# hall_sensor100a.net
KiCad netlist of a schematic drawn in EAGLE
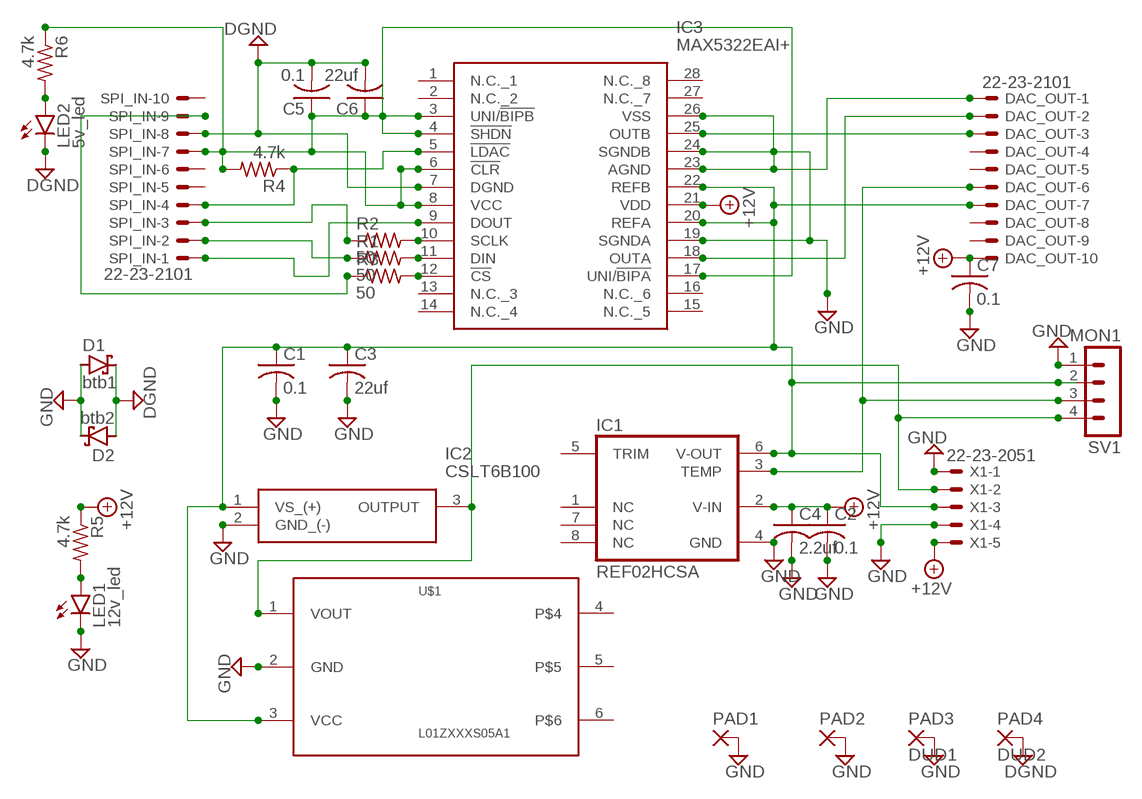
[diagram p0: schematic, sheet 1]

(export (version "E")
  (design (tool "Eeschema 10.0.6"))
  (components
    (comp (ref "C1")
      (value "0.1")
      (footprint "eagle-import:C0805")
      (libsource (lib "eagle-import") (part "C-USC0805"))
    )
    (comp (ref "C2")
      (value "0.1")
      (footprint "eagle-import:C0805")
      (libsource (lib "eagle-import") (part "C-USC0805"))
    )
    (comp (ref "C3")
      (value "22uf")
      (footprint "eagle-import:C0805")
      (libsource (lib "eagle-import") (part "C-USC0805"))
    )
    (comp (ref "C4")
      (value "2.2uf")
      (footprint "eagle-import:C0805")
      (libsource (lib "eagle-import") (part "C-USC0805"))
    )
    (comp (ref "C5")
      (value "0.1")
      (footprint "eagle-import:C0805")
      (libsource (lib "eagle-import") (part "C-USC0805"))
    )
    (comp (ref "C6")
      (value "22uf")
      (footprint "eagle-import:C0805")
      (libsource (lib "eagle-import") (part "C-USC0805"))
    )
    (comp (ref "C7")
      (value "0.1")
      (footprint "eagle-import:C0805")
      (libsource (lib "eagle-import") (part "C-USC0805"))
    )
    (comp (ref "D1")
      (value "btb1")
      (footprint "eagle-import:DO35-7")
      (libsource (lib "eagle-import") (part "SCHOTTKY-DIODEDO35-7"))
    )
    (comp (ref "D2")
      (value "btb2")
      (footprint "eagle-import:DO35-7")
      (libsource (lib "eagle-import") (part "SCHOTTKY-DIODEDO35-7"))
    )
    (comp (ref "DAC_OUT")
      (value "22-23-2101")
      (footprint "eagle-import:22-23-2101")
      (fields (field (name "MF") "MOLEX"))
      (libsource (lib "eagle-import") (part "22-23-2101"))
    )
    (comp (ref "IC1")
      (value "REF02HCSA")
      (footprint "eagle-import:SO08")
      (libsource (lib "eagle-import") (part "REF02HCSA"))
    )
    (comp (ref "IC2")
      (value "CSLT6B100")
      (footprint "eagle-import:CSLT6B100")
      (fields (field (name "MOUSER_PART_NUMBER") "785-CSLT6B100"))
      (libsource (lib "eagle-import") (part "CSLT6B100"))
    )
    (comp (ref "IC3")
      (value "MAX5322EAI+")
      (footprint "eagle-import:SOP65P778X199-28N")
      (fields (field (name "MOUSER_PART_NUMBER") "700-MAX5322EAI") (field (name "RS_PART_NUMBER") "7997645P"))
      (libsource (lib "eagle-import") (part "MAX5322EAI+"))
    )
    (comp (ref "LED1")
      (value "12v_led")
      (footprint "eagle-import:CHIPLED_1206")
      (libsource (lib "eagle-import") (part "LEDCHIPLED_1206"))
    )
    (comp (ref "LED2")
      (value "5v_led")
      (footprint "eagle-import:CHIPLED_1206")
      (libsource (lib "eagle-import") (part "LEDCHIPLED_1206"))
    )
    (comp (ref "PAD1")
      (value "2,15/1,0")
      (footprint "eagle-import:2,15_1,0")
      (libsource (lib "eagle-import") (part "2,15/1,0"))
    )
    (comp (ref "PAD2")
      (value "2,15/1,0")
      (footprint "eagle-import:2,15_1,0")
      (libsource (lib "eagle-import") (part "2,15/1,0"))
    )
    (comp (ref "PAD3")
      (value "DUD1")
      (footprint "eagle-import:2,15_1,0")
      (libsource (lib "eagle-import") (part "2,15/1,0"))
    )
    (comp (ref "PAD4")
      (value "DUD2")
      (footprint "eagle-import:2,15_1,0")
      (libsource (lib "eagle-import") (part "2,15/1,0"))
    )
    (comp (ref "R1")
      (value "50")
      (footprint "eagle-import:M0805")
      (libsource (lib "eagle-import") (part "R-US_M0805"))
    )
    (comp (ref "R2")
      (value "50")
      (footprint "eagle-import:M0805")
      (libsource (lib "eagle-import") (part "R-US_M0805"))
    )
    (comp (ref "R3")
      (value "50")
      (footprint "eagle-import:M0805")
      (libsource (lib "eagle-import") (part "R-US_M0805"))
    )
    (comp (ref "R4")
      (value "4.7k")
      (footprint "eagle-import:M0805")
      (libsource (lib "eagle-import") (part "R-US_M0805"))
    )
    (comp (ref "R5")
      (value "4.7k")
      (footprint "eagle-import:M0805")
      (libsource (lib "eagle-import") (part "R-US_M0805"))
    )
    (comp (ref "R6")
      (value "4.7k")
      (footprint "eagle-import:M0805")
      (libsource (lib "eagle-import") (part "R-US_M0805"))
    )
    (comp (ref "SPI_IN")
      (value "22-23-2101")
      (footprint "eagle-import:22-23-2101")
      (fields (field (name "MF") "MOLEX"))
      (libsource (lib "eagle-import") (part "22-23-2101"))
    )
    (comp (ref "SV1")
      (value "MON1")
      (footprint "eagle-import:MA04-1")
      (libsource (lib "eagle-import") (part "MA04-1"))
    )
    (comp (ref "U$1")
      (value "L01ZXXXS05A1")
      (footprint "eagle-import:DIP2540W53P254L2900H508Q6B")
      (libsource (lib "eagle-import") (part "L01ZXXXS05A1"))
    )
    (comp (ref "X1")
      (value "22-23-2051")
      (footprint "eagle-import:22-23-2051")
      (fields (field (name "MF") "MOLEX"))
      (libsource (lib "eagle-import") (part "22-23-2051"))
    )
  )
  (nets
    (net (code "1") (name "+12V") (class "Default")
      (node (ref "C2") (pin "1") (pinfunction "1_1") (pintype "passive"))
      (node (ref "C4") (pin "1") (pinfunction "1_1") (pintype "passive"))
      (node (ref "C7") (pin "1") (pinfunction "1_1") (pintype "passive"))
      (node (ref "DAC_OUT") (pin "10") (pinfunction "S_10") (pintype "passive"))
      (node (ref "IC1") (pin "2") (pinfunction "V-IN_2") (pintype "power_in"))
      (node (ref "IC3") (pin "21") (pinfunction "VDD_21") (pintype "bidirectional"))
      (node (ref "R5") (pin "1") (pinfunction "1_1") (pintype "passive"))
      (node (ref "X1") (pin "5") (pinfunction "S_5") (pintype "passive"))
    )
    (net (code "2") (name "DGND") (class "Default")
      (node (ref "C5") (pin "2") (pinfunction "2_2") (pintype "passive"))
      (node (ref "C6") (pin "2") (pinfunction "2_2") (pintype "passive"))
      (node (ref "D1") (pin "C") (pinfunction "C_C") (pintype "passive"))
      (node (ref "D2") (pin "A") (pinfunction "A_A") (pintype "passive"))
      (node (ref "IC3") (pin "7") (pinfunction "DGND_7") (pintype "bidirectional"))
      (node (ref "LED2") (pin "C") (pinfunction "C_C") (pintype "passive"))
      (node (ref "PAD4") (pin "1") (pinfunction "P_1") (pintype "passive"))
      (node (ref "SPI_IN") (pin "8") (pinfunction "S_8") (pintype "passive"))
    )
    (net (code "3") (name "GND") (class "Default")
      (node (ref "C1") (pin "2") (pinfunction "2_2") (pintype "passive"))
      (node (ref "C2") (pin "2") (pinfunction "2_2") (pintype "passive"))
      (node (ref "C3") (pin "2") (pinfunction "2_2") (pintype "passive"))
      (node (ref "C4") (pin "2") (pinfunction "2_2") (pintype "passive"))
      (node (ref "C7") (pin "2") (pinfunction "2_2") (pintype "passive"))
      (node (ref "D1") (pin "A") (pinfunction "A_A") (pintype "passive"))
      (node (ref "D2") (pin "C") (pinfunction "C_C") (pintype "passive"))
      (node (ref "DAC_OUT") (pin "1") (pinfunction "S_1") (pintype "passive"))
      (node (ref "IC1") (pin "4") (pinfunction "GND_4") (pintype "power_in"))
      (node (ref "IC2") (pin "2") (pinfunction "GND_(-)_2") (pintype "bidirectional"))
      (node (ref "IC3") (pin "19") (pinfunction "SGNDA_19") (pintype "bidirectional"))
      (node (ref "IC3") (pin "23") (pinfunction "AGND_23") (pintype "bidirectional"))
      (node (ref "IC3") (pin "24") (pinfunction "SGNDB_24") (pintype "bidirectional"))
      (node (ref "IC3") (pin "26") (pinfunction "VSS_26") (pintype "bidirectional"))
      (node (ref "LED1") (pin "C") (pinfunction "C_C") (pintype "passive"))
      (node (ref "PAD1") (pin "1") (pinfunction "P_1") (pintype "passive"))
      (node (ref "PAD2") (pin "1") (pinfunction "P_1") (pintype "passive"))
      (node (ref "PAD3") (pin "1") (pinfunction "P_1") (pintype "passive"))
      (node (ref "SV1") (pin "1") (pinfunction "1_1") (pintype "passive"))
      (node (ref "U$1") (pin "2") (pinfunction "GND_2") (pintype "power_in"))
      (node (ref "X1") (pin "1") (pinfunction "S_1") (pintype "passive"))
      (node (ref "X1") (pin "4") (pinfunction "S_4") (pintype "passive"))
    )
    (net (code "4") (name "Net-(DAC_OUTC-S)") (class "Default")
      (node (ref "DAC_OUT") (pin "2") (pinfunction "S_2") (pintype "passive"))
      (node (ref "IC3") (pin "18") (pinfunction "OUTA_18") (pintype "bidirectional"))
    )
    (net (code "5") (name "Net-(DAC_OUTD-S)") (class "Default")
      (node (ref "DAC_OUT") (pin "3") (pinfunction "S_3") (pintype "passive"))
      (node (ref "IC3") (pin "25") (pinfunction "OUTB_25") (pintype "bidirectional"))
    )
    (net (code "6") (name "Net-(DAC_OUTG-S)") (class "Default")
      (node (ref "DAC_OUT") (pin "6") (pinfunction "S_6") (pintype "passive"))
      (node (ref "IC1") (pin "3") (pinfunction "TEMP_3") (pintype "output"))
      (node (ref "SV1") (pin "3") (pinfunction "3_3") (pintype "passive"))
    )
    (net (code "7") (name "Net-(DAC_OUTH-S)") (class "Default")
      (node (ref "C1") (pin "1") (pinfunction "1_1") (pintype "passive"))
      (node (ref "C3") (pin "1") (pinfunction "1_1") (pintype "passive"))
      (node (ref "DAC_OUT") (pin "7") (pinfunction "S_7") (pintype "passive"))
      (node (ref "IC1") (pin "6") (pinfunction "V-OUT_6") (pintype "output"))
      (node (ref "IC2") (pin "1") (pinfunction "VS_(+)_1") (pintype "bidirectional"))
      (node (ref "IC3") (pin "20") (pinfunction "REFA_20") (pintype "bidirectional"))
      (node (ref "IC3") (pin "22") (pinfunction "REFB_22") (pintype "bidirectional"))
      (node (ref "SV1") (pin "2") (pinfunction "2_2") (pintype "passive"))
      (node (ref "U$1") (pin "3") (pinfunction "VCC_3") (pintype "power_in"))
      (node (ref "X1") (pin "3") (pinfunction "S_3") (pintype "passive"))
    )
    (net (code "8") (name "Net-(IC2-OUTPUT)") (class "Default")
      (node (ref "IC2") (pin "3") (pinfunction "OUTPUT_3") (pintype "bidirectional"))
      (node (ref "SV1") (pin "4") (pinfunction "4_4") (pintype "passive"))
      (node (ref "U$1") (pin "1") (pinfunction "VOUT_1") (pintype "output"))
      (node (ref "X1") (pin "2") (pinfunction "S_2") (pintype "passive"))
    )
    (net (code "9") (name "Net-(IC3-DIN)") (class "Default")
      (node (ref "IC3") (pin "11") (pinfunction "DIN_11") (pintype "bidirectional"))
      (node (ref "R1") (pin "2") (pinfunction "2_2") (pintype "passive"))
    )
    (net (code "10") (name "Net-(IC3-DOUT)") (class "Default")
      (node (ref "IC3") (pin "9") (pinfunction "DOUT_9") (pintype "bidirectional"))
      (node (ref "SPI_IN") (pin "1") (pinfunction "S_1") (pintype "passive"))
    )
    (net (code "11") (name "Net-(IC3-SCLK)") (class "Default")
      (node (ref "IC3") (pin "10") (pinfunction "SCLK_10") (pintype "bidirectional"))
      (node (ref "R2") (pin "2") (pinfunction "2_2") (pintype "passive"))
    )
    (net (code "12") (name "Net-(IC3-UNI{slash}~{BIPA})") (class "Default")
      (node (ref "C5") (pin "1") (pinfunction "1_1") (pintype "passive"))
      (node (ref "C6") (pin "1") (pinfunction "1_1") (pintype "passive"))
      (node (ref "IC3") (pin "17") (pinfunction "UNI/~{BIPA}_17") (pintype "bidirectional"))
      (node (ref "IC3") (pin "3") (pinfunction "UNI/~{BIPB}_3") (pintype "bidirectional"))
      (node (ref "IC3") (pin "4") (pinfunction "~{SHDN}_4") (pintype "bidirectional"))
      (node (ref "IC3") (pin "6") (pinfunction "~{CLR}_6") (pintype "bidirectional"))
      (node (ref "IC3") (pin "8") (pinfunction "VCC_8") (pintype "bidirectional"))
      (node (ref "R4") (pin "2") (pinfunction "2_2") (pintype "passive"))
      (node (ref "R6") (pin "1") (pinfunction "1_1") (pintype "passive"))
      (node (ref "SPI_IN") (pin "7") (pinfunction "S_7") (pintype "passive"))
    )
    (net (code "13") (name "Net-(IC3-~{CS})") (class "Default")
      (node (ref "IC3") (pin "12") (pinfunction "~{CS}_12") (pintype "bidirectional"))
      (node (ref "R3") (pin "2") (pinfunction "2_2") (pintype "passive"))
    )
    (net (code "14") (name "Net-(IC3-~{LDAC})") (class "Default")
      (node (ref "IC3") (pin "5") (pinfunction "~{LDAC}_5") (pintype "bidirectional"))
      (node (ref "R4") (pin "1") (pinfunction "1_1") (pintype "passive"))
      (node (ref "SPI_IN") (pin "4") (pinfunction "S_4") (pintype "passive"))
    )
    (net (code "15") (name "Net-(LED1-PadA)") (class "Default")
      (node (ref "LED1") (pin "A") (pinfunction "A_A") (pintype "passive"))
      (node (ref "R5") (pin "2") (pinfunction "2_2") (pintype "passive"))
    )
    (net (code "16") (name "Net-(LED2-PadA)") (class "Default")
      (node (ref "LED2") (pin "A") (pinfunction "A_A") (pintype "passive"))
      (node (ref "R6") (pin "2") (pinfunction "2_2") (pintype "passive"))
    )
    (net (code "17") (name "Net-(SPI_INC-S)") (class "Default")
      (node (ref "R1") (pin "1") (pinfunction "1_1") (pintype "passive"))
      (node (ref "SPI_IN") (pin "2") (pinfunction "S_2") (pintype "passive"))
    )
    (net (code "18") (name "Net-(SPI_IND-S)") (class "Default")
      (node (ref "R2") (pin "1") (pinfunction "1_1") (pintype "passive"))
      (node (ref "SPI_IN") (pin "3") (pinfunction "S_3") (pintype "passive"))
    )
    (net (code "19") (name "Net-(SPI_INJ-S)") (class "Default")
      (node (ref "R3") (pin "1") (pinfunction "1_1") (pintype "passive"))
      (node (ref "SPI_IN") (pin "9") (pinfunction "S_9") (pintype "passive"))
    )
    (net (code "20") (name "unconnected-(DAC_OUTE-S-Pad4)") (class "Default")
      (node (ref "DAC_OUT") (pin "4") (pinfunction "S_4") (pintype "passive"))
    )
    (net (code "21") (name "unconnected-(DAC_OUTF-S-Pad5)") (class "Default")
      (node (ref "DAC_OUT") (pin "5") (pinfunction "S_5") (pintype "passive"))
    )
    (net (code "22") (name "unconnected-(DAC_OUTI-S-Pad8)") (class "Default")
      (node (ref "DAC_OUT") (pin "8") (pinfunction "S_8") (pintype "passive"))
    )
    (net (code "23") (name "unconnected-(DAC_OUTJ-S-Pad9)") (class "Default")
      (node (ref "DAC_OUT") (pin "9") (pinfunction "S_9") (pintype "passive"))
    )
    (net (code "24") (name "unconnected-(IC1-NC-Pad1)") (class "Default")
      (node (ref "IC1") (pin "1") (pinfunction "NC_1") (pintype "no_connect"))
    )
    (net (code "25") (name "unconnected-(IC1-NC-Pad7)") (class "Default")
      (node (ref "IC1") (pin "7") (pinfunction "NC_7") (pintype "no_connect"))
    )
    (net (code "26") (name "unconnected-(IC1-NC-Pad8)") (class "Default")
      (node (ref "IC1") (pin "8") (pinfunction "NC_8") (pintype "no_connect"))
    )
    (net (code "27") (name "unconnected-(IC1-TRIM-Pad5)") (class "Default")
      (node (ref "IC1") (pin "5") (pinfunction "TRIM_5") (pintype "input"))
    )
    (net (code "28") (name "unconnected-(IC3-N.C._1-Pad1)") (class "Default")
      (node (ref "IC3") (pin "1") (pinfunction "N.C._1_1") (pintype "bidirectional"))
    )
    (net (code "29") (name "unconnected-(IC3-N.C._2-Pad2)") (class "Default")
      (node (ref "IC3") (pin "2") (pinfunction "N.C._2_2") (pintype "bidirectional"))
    )
    (net (code "30") (name "unconnected-(IC3-N.C._3-Pad13)") (class "Default")
      (node (ref "IC3") (pin "13") (pinfunction "N.C._3_13") (pintype "bidirectional"))
    )
    (net (code "31") (name "unconnected-(IC3-N.C._4-Pad14)") (class "Default")
      (node (ref "IC3") (pin "14") (pinfunction "N.C._4_14") (pintype "bidirectional"))
    )
    (net (code "32") (name "unconnected-(IC3-N.C._5-Pad15)") (class "Default")
      (node (ref "IC3") (pin "15") (pinfunction "N.C._5_15") (pintype "bidirectional"))
    )
    (net (code "33") (name "unconnected-(IC3-N.C._6-Pad16)") (class "Default")
      (node (ref "IC3") (pin "16") (pinfunction "N.C._6_16") (pintype "bidirectional"))
    )
    (net (code "34") (name "unconnected-(IC3-N.C._7-Pad27)") (class "Default")
      (node (ref "IC3") (pin "27") (pinfunction "N.C._7_27") (pintype "bidirectional"))
    )
    (net (code "35") (name "unconnected-(IC3-N.C._8-Pad28)") (class "Default")
      (node (ref "IC3") (pin "28") (pinfunction "N.C._8_28") (pintype "bidirectional"))
    )
    (net (code "36") (name "unconnected-(SPI_INB-S-Pad10)") (class "Default")
      (node (ref "SPI_IN") (pin "10") (pinfunction "S_10") (pintype "passive"))
    )
    (net (code "37") (name "unconnected-(SPI_INF-S-Pad5)") (class "Default")
      (node (ref "SPI_IN") (pin "5") (pinfunction "S_5") (pintype "passive"))
    )
    (net (code "38") (name "unconnected-(SPI_ING-S-Pad6)") (class "Default")
      (node (ref "SPI_IN") (pin "6") (pinfunction "S_6") (pintype "passive"))
    )
    (net (code "39") (name "unconnected-(U$1-P$4-Pad4)") (class "Default")
      (node (ref "U$1") (pin "4") (pinfunction "P$4_4") (pintype "no_connect"))
    )
    (net (code "40") (name "unconnected-(U$1-P$5-Pad5)") (class "Default")
      (node (ref "U$1") (pin "5") (pinfunction "P$5_5") (pintype "no_connect"))
    )
    (net (code "41") (name "unconnected-(U$1-P$6-Pad6)") (class "Default")
      (node (ref "U$1") (pin "6") (pinfunction "P$6_6") (pintype "no_connect"))
    )
  )
)
